# LCL_2.net
KiCad netlist of a schematic drawn in Altium Designer
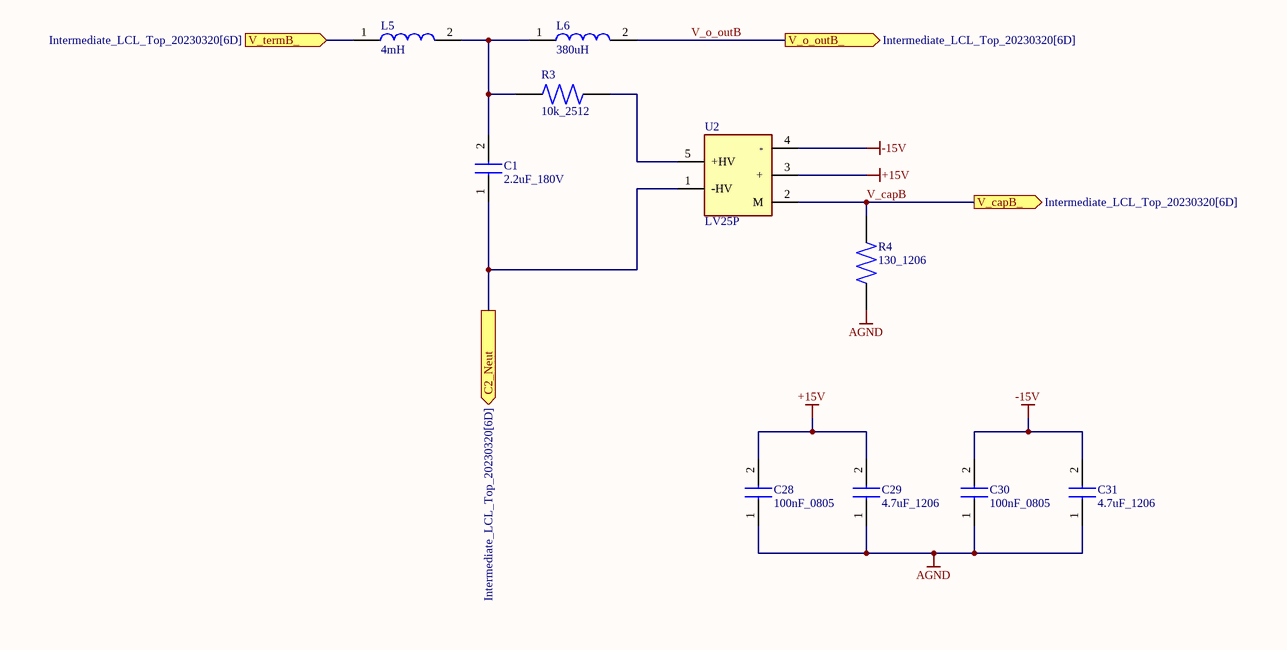
[diagram p0: LCL_2.SchDoc]

(export (version "E")
  (design (tool "Eeschema 10.0.6"))
  (components
    (comp (ref "C1")
      (value "2.2uF_180V")
      (footprint "Film Capacitor PHE450HF7220JR06L2")
      (description "KEMET PHE450 Metallised Polypropylene Film Capacitor, 180 V ac, 250 V dc, ±5%, 2.2μF, Through Hole")
      (fields (field (name "MANUFACTURER_PART_NUMBER") "PHE450HF7220JR06L2"))
      (libsource (lib "FYP_Components") (part "PHE450HF7220JR06L2"))
    )
    (comp (ref "C28")
      (value "100nF_0805")
      (footprint "0805 Capacitor")
      (description "SMD Multilayer Ceramic Capacitor, 0.1 µF, 50 V, 0805 [2012 Metric], ± 5%, X7R, C Series KEMET")
      (libsource (lib "FYP_Components") (part "C0805C104J5RACTU"))
    )
    (comp (ref "C29")
      (value "4.7uF_1206")
      (footprint "FYP_Components:1206 Capacitor")
      (description "SMD Multilayer Ceramic Capacitor, 4.7 µF, 50 V, 1206 [3216 Metric], ± 10%, X7R, C")
      (fields (field (name "MP") "C1206C120J5GACTU"))
      (libsource (lib "FYP_Components") (part "C3216X7R1H475K160AC"))
    )
    (comp (ref "C30")
      (value "100nF_0805")
      (footprint "0805 Capacitor")
      (description "SMD Multilayer Ceramic Capacitor, 0.1 µF, 50 V, 0805 [2012 Metric], ± 5%, X7R, C Series KEMET")
      (libsource (lib "FYP_Components") (part "C0805C104J5RACTU"))
    )
    (comp (ref "C31")
      (value "4.7uF_1206")
      (footprint "FYP_Components:1206 Capacitor")
      (description "SMD Multilayer Ceramic Capacitor, 4.7 µF, 50 V, 1206 [3216 Metric], ± 10%, X7R, C")
      (fields (field (name "MP") "C1206C120J5GACTU"))
      (libsource (lib "FYP_Components") (part "C3216X7R1H475K160AC"))
    )
    (comp (ref "L5")
      (value "4mH")
      (footprint "4mH Custom")
      (libsource (lib "FYP_Components") (part "4mH Custom Inductor"))
    )
    (comp (ref "L6")
      (value "380uH")
      (footprint "380uH Custom")
      (libsource (lib "FYP_Components") (part "380uH Custom Inductor"))
    )
    (comp (ref "R3")
      (value "10k_2512")
      (footprint "FYP_Components:2512 Resistor")
      (description "SMD Chip Resistor, 10 kohm, ± 1%, 2 W, 2512 [6432 Metric], Thick Film, High Power")
      (fields (field (name "MF") "Bourns") (field (name "MP") "CRE2512-FZ-R007E-3"))
      (libsource (lib "FYP_Components") (part "MCHP122WF1002T4E"))
    )
    (comp (ref "R4")
      (value "130_1206")
      (footprint "FYP_Components:1206 Resistor")
      (description "SMD Chip Resistor, 130 ohm, ± 1%, 250 mW, 1206 [3216 Metric], Thick Film, General Purpose")
      (fields (field (name "MF") "Bourns") (field (name "MP") "CRE2512-FZ-R007E-3"))
      (libsource (lib "FYP_Components") (part "CRCW1206130RFKEA"))
    )
    (comp (ref "U2")
      (value "LV25P")
      (footprint "FYP_Components:LV-25-P")
      (description "Undefined or Miscellaneous")
      (libsource (lib "FYP_Components") (part "LV25P"))
    )
  )
  (nets
    (net (code "1") (name "+15V") (class "Default")
      (node (ref "C28") (pin "2") (pinfunction "2_2") (pintype "passive"))
      (node (ref "C29") (pin "2") (pinfunction "2_2") (pintype "passive"))
      (node (ref "U2") (pin "3") (pinfunction "+_3") (pintype "passive"))
    )
    (net (code "2") (name "-15V") (class "Default")
      (node (ref "C30") (pin "2") (pinfunction "2_2") (pintype "passive"))
      (node (ref "C31") (pin "2") (pinfunction "2_2") (pintype "passive"))
      (node (ref "U2") (pin "4") (pinfunction "-_4") (pintype "passive"))
    )
    (net (code "3") (name "/C2_Neut") (class "Default")
      (node (ref "C1") (pin "1") (pinfunction "1_1") (pintype "passive"))
      (node (ref "U2") (pin "1") (pinfunction "-HV_1") (pintype "passive"))
    )
    (net (code "4") (name "/V_capB") (class "Default")
      (node (ref "R4") (pin "2") (pinfunction "2_2") (pintype "passive"))
      (node (ref "U2") (pin "2") (pinfunction "M_2") (pintype "passive"))
    )
    (net (code "5") (name "/V_o_outB") (class "Default")
      (node (ref "L6") (pin "2") (pinfunction "2_2") (pintype "passive"))
    )
    (net (code "6") (name "/V_termB_") (class "Default")
      (node (ref "L5") (pin "1") (pinfunction "1_1") (pintype "passive"))
    )
    (net (code "7") (name "AGND") (class "Default")
      (node (ref "C28") (pin "1") (pinfunction "1_1") (pintype "passive"))
      (node (ref "C29") (pin "1") (pinfunction "1_1") (pintype "passive"))
      (node (ref "C30") (pin "1") (pinfunction "1_1") (pintype "passive"))
      (node (ref "C31") (pin "1") (pinfunction "1_1") (pintype "passive"))
      (node (ref "R4") (pin "1") (pinfunction "1_1") (pintype "passive"))
    )
    (net (code "8") (name "Net-(C1-Pad2)") (class "Default")
      (node (ref "C1") (pin "2") (pinfunction "2_2") (pintype "passive"))
      (node (ref "L5") (pin "2") (pinfunction "2_2") (pintype "passive"))
      (node (ref "L6") (pin "1") (pinfunction "1_1") (pintype "passive"))
      (node (ref "R3") (pin "1") (pinfunction "1_1") (pintype "passive"))
    )
    (net (code "9") (name "Net-(U2-+HV)") (class "Default")
      (node (ref "R3") (pin "2") (pinfunction "2_2") (pintype "passive"))
      (node (ref "U2") (pin "5") (pinfunction "+HV_5") (pintype "passive"))
    )
  )
)
